# LSA-PCB_4xSerial_Analog.net
KiCad netlist of a schematic drawn in EAGLE
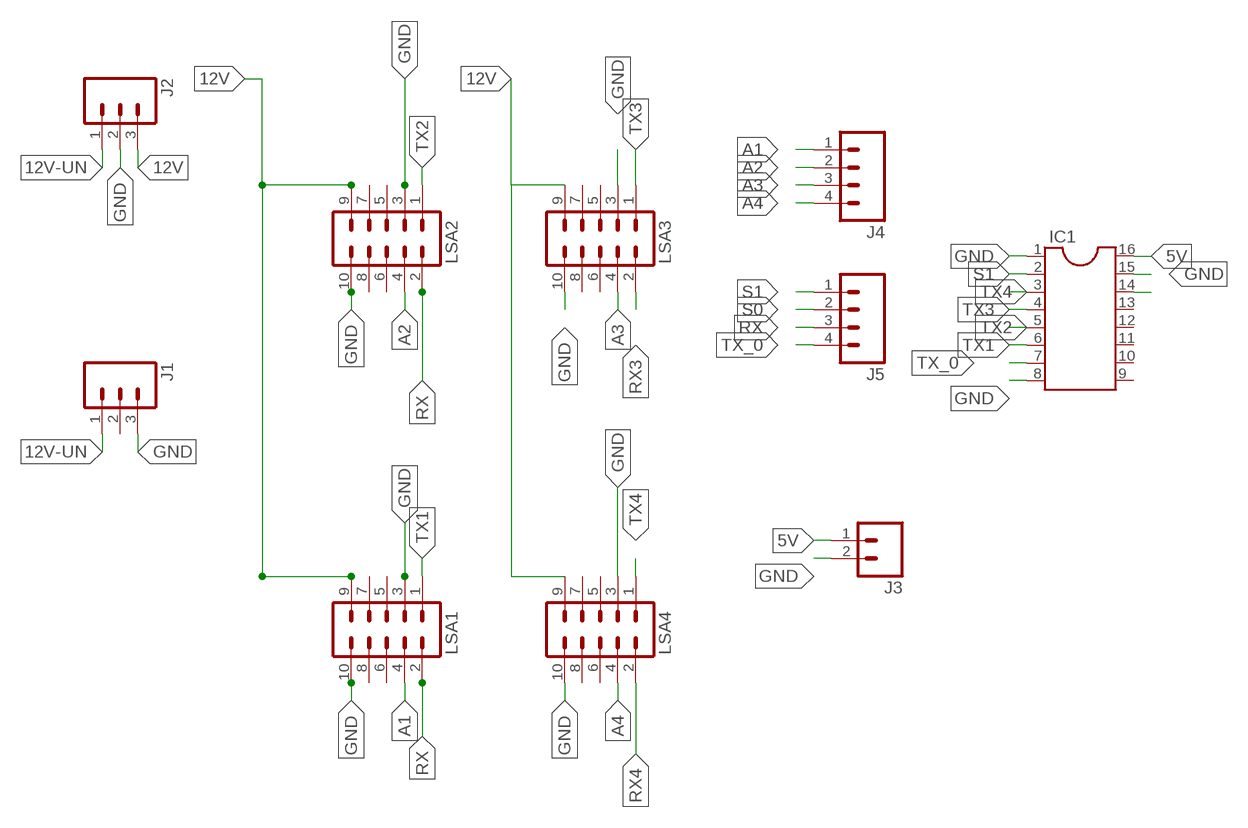
[diagram p0: schematic, sheet 1]

(export (version "E")
  (design (tool "Eeschema 10.0.6"))
  (components
    (comp (ref "IC1")
      (value "DIL16S")
      (footprint "eagle-import:SOCKET-16")
      (libsource (lib "eagle-import") (part "DIL16S"))
    )
    (comp (ref "J1")
      (value "M03PTH")
      (footprint "eagle-import:1X03")
      (libsource (lib "eagle-import") (part "M03PTH"))
    )
    (comp (ref "J2")
      (value "M03PTH")
      (footprint "eagle-import:1X03")
      (libsource (lib "eagle-import") (part "M03PTH"))
    )
    (comp (ref "J3")
      (value "M02PTH")
      (footprint "eagle-import:1X02")
      (libsource (lib "eagle-import") (part "M02PTH"))
    )
    (comp (ref "J4")
      (value "M04PTH")
      (footprint "eagle-import:1X04")
      (libsource (lib "eagle-import") (part "M04PTH"))
    )
    (comp (ref "J5")
      (value "M04PTH")
      (footprint "eagle-import:1X04")
      (libsource (lib "eagle-import") (part "M04PTH"))
    )
    (comp (ref "LSA1")
      (value "M05X2SHD_LOCK")
      (footprint "eagle-import:2X5-SHROUDED_LOCK")
      (libsource (lib "eagle-import") (part "M05X2SHD_LOCK"))
    )
    (comp (ref "LSA2")
      (value "M05X2SHD_LOCK")
      (footprint "eagle-import:2X5-SHROUDED_LOCK")
      (libsource (lib "eagle-import") (part "M05X2SHD_LOCK"))
    )
    (comp (ref "LSA3")
      (value "M05X2SHD_LOCK")
      (footprint "eagle-import:2X5-SHROUDED_LOCK")
      (libsource (lib "eagle-import") (part "M05X2SHD_LOCK"))
    )
    (comp (ref "LSA4")
      (value "M05X2SHD_LOCK")
      (footprint "eagle-import:2X5-SHROUDED_LOCK")
      (libsource (lib "eagle-import") (part "M05X2SHD_LOCK"))
    )
  )
  (nets
    (net (code "1") (name "5V") (class "Default")
      (node (ref "IC1") (pin "16") (pinfunction "16_16") (pintype "passive"))
      (node (ref "J3") (pin "1") (pinfunction "1_1") (pintype "passive"))
    )
    (net (code "2") (name "12V") (class "Default")
      (node (ref "J2") (pin "3") (pinfunction "3_3") (pintype "passive"))
      (node (ref "LSA1") (pin "9") (pinfunction "9_9") (pintype "passive"))
      (node (ref "LSA2") (pin "9") (pinfunction "9_9") (pintype "passive"))
      (node (ref "LSA3") (pin "9") (pinfunction "9_9") (pintype "passive"))
      (node (ref "LSA4") (pin "9") (pinfunction "9_9") (pintype "passive"))
    )
    (net (code "3") (name "12V-UN") (class "Default")
      (node (ref "J1") (pin "1") (pinfunction "1_1") (pintype "passive"))
      (node (ref "J2") (pin "1") (pinfunction "1_1") (pintype "passive"))
    )
    (net (code "4") (name "A1") (class "Default")
      (node (ref "J4") (pin "1") (pinfunction "1_1") (pintype "passive"))
      (node (ref "LSA1") (pin "4") (pinfunction "4_4") (pintype "passive"))
    )
    (net (code "5") (name "A2") (class "Default")
      (node (ref "J4") (pin "2") (pinfunction "2_2") (pintype "passive"))
      (node (ref "LSA2") (pin "4") (pinfunction "4_4") (pintype "passive"))
    )
    (net (code "6") (name "A3") (class "Default")
      (node (ref "J4") (pin "3") (pinfunction "3_3") (pintype "passive"))
      (node (ref "LSA3") (pin "4") (pinfunction "4_4") (pintype "passive"))
    )
    (net (code "7") (name "A4") (class "Default")
      (node (ref "J4") (pin "4") (pinfunction "4_4") (pintype "passive"))
      (node (ref "LSA4") (pin "4") (pinfunction "4_4") (pintype "passive"))
    )
    (net (code "8") (name "GND") (class "Default")
      (node (ref "IC1") (pin "1") (pinfunction "1_1") (pintype "passive"))
      (node (ref "IC1") (pin "15") (pinfunction "15_15") (pintype "passive"))
      (node (ref "IC1") (pin "8") (pinfunction "8_8") (pintype "passive"))
      (node (ref "J1") (pin "3") (pinfunction "3_3") (pintype "passive"))
      (node (ref "J2") (pin "2") (pinfunction "2_2") (pintype "passive"))
      (node (ref "J3") (pin "2") (pinfunction "2_2") (pintype "passive"))
      (node (ref "LSA1") (pin "10") (pinfunction "10_10") (pintype "passive"))
      (node (ref "LSA1") (pin "3") (pinfunction "3_3") (pintype "passive"))
      (node (ref "LSA2") (pin "10") (pinfunction "10_10") (pintype "passive"))
      (node (ref "LSA2") (pin "3") (pinfunction "3_3") (pintype "passive"))
      (node (ref "LSA3") (pin "10") (pinfunction "10_10") (pintype "passive"))
      (node (ref "LSA3") (pin "3") (pinfunction "3_3") (pintype "passive"))
      (node (ref "LSA4") (pin "10") (pinfunction "10_10") (pintype "passive"))
      (node (ref "LSA4") (pin "3") (pinfunction "3_3") (pintype "passive"))
    )
    (net (code "9") (name "RX") (class "Default")
      (node (ref "J5") (pin "3") (pinfunction "3_3") (pintype "passive"))
      (node (ref "LSA1") (pin "2") (pinfunction "2_2") (pintype "passive"))
      (node (ref "LSA2") (pin "2") (pinfunction "2_2") (pintype "passive"))
    )
    (net (code "10") (name "RX3") (class "Default")
      (node (ref "LSA3") (pin "2") (pinfunction "2_2") (pintype "passive"))
    )
    (net (code "11") (name "RX4") (class "Default")
      (node (ref "LSA4") (pin "2") (pinfunction "2_2") (pintype "passive"))
    )
    (net (code "12") (name "S0") (class "Default")
      (node (ref "IC1") (pin "14") (pinfunction "14_14") (pintype "passive"))
      (node (ref "J5") (pin "2") (pinfunction "2_2") (pintype "passive"))
    )
    (net (code "13") (name "S1") (class "Default")
      (node (ref "IC1") (pin "2") (pinfunction "2_2") (pintype "passive"))
      (node (ref "J5") (pin "1") (pinfunction "1_1") (pintype "passive"))
    )
    (net (code "14") (name "TX1") (class "Default")
      (node (ref "IC1") (pin "6") (pinfunction "6_6") (pintype "passive"))
      (node (ref "LSA1") (pin "1") (pinfunction "1_1") (pintype "passive"))
    )
    (net (code "15") (name "TX2") (class "Default")
      (node (ref "IC1") (pin "5") (pinfunction "5_5") (pintype "passive"))
      (node (ref "LSA2") (pin "1") (pinfunction "1_1") (pintype "passive"))
    )
    (net (code "16") (name "TX3") (class "Default")
      (node (ref "IC1") (pin "4") (pinfunction "4_4") (pintype "passive"))
      (node (ref "LSA3") (pin "1") (pinfunction "1_1") (pintype "passive"))
    )
    (net (code "17") (name "TX4") (class "Default")
      (node (ref "IC1") (pin "3") (pinfunction "3_3") (pintype "passive"))
      (node (ref "LSA4") (pin "1") (pinfunction "1_1") (pintype "passive"))
    )
    (net (code "18") (name "TX_0") (class "Default")
      (node (ref "IC1") (pin "7") (pinfunction "7_7") (pintype "passive"))
      (node (ref "J5") (pin "4") (pinfunction "4_4") (pintype "passive"))
    )
    (net (code "19") (name "unconnected-(IC1-Pad9)") (class "Default")
      (node (ref "IC1") (pin "9") (pinfunction "9_9") (pintype "passive"))
    )
    (net (code "20") (name "unconnected-(IC1-Pad10)") (class "Default")
      (node (ref "IC1") (pin "10") (pinfunction "10_10") (pintype "passive"))
    )
    (net (code "21") (name "unconnected-(IC1-Pad11)") (class "Default")
      (node (ref "IC1") (pin "11") (pinfunction "11_11") (pintype "passive"))
    )
    (net (code "22") (name "unconnected-(IC1-Pad12)") (class "Default")
      (node (ref "IC1") (pin "12") (pinfunction "12_12") (pintype "passive"))
    )
    (net (code "23") (name "unconnected-(IC1-Pad13)") (class "Default")
      (node (ref "IC1") (pin "13") (pinfunction "13_13") (pintype "passive"))
    )
    (net (code "24") (name "unconnected-(J1-Pad2)") (class "Default")
      (node (ref "J1") (pin "2") (pinfunction "2_2") (pintype "passive"))
    )
    (net (code "25") (name "unconnected-(LSA1-Pad5)") (class "Default")
      (node (ref "LSA1") (pin "5") (pinfunction "5_5") (pintype "passive"))
    )
    (net (code "26") (name "unconnected-(LSA1-Pad6)") (class "Default")
      (node (ref "LSA1") (pin "6") (pinfunction "6_6") (pintype "passive"))
    )
    (net (code "27") (name "unconnected-(LSA1-Pad7)") (class "Default")
      (node (ref "LSA1") (pin "7") (pinfunction "7_7") (pintype "passive"))
    )
    (net (code "28") (name "unconnected-(LSA1-Pad8)") (class "Default")
      (node (ref "LSA1") (pin "8") (pinfunction "8_8") (pintype "passive"))
    )
    (net (code "29") (name "unconnected-(LSA2-Pad5)") (class "Default")
      (node (ref "LSA2") (pin "5") (pinfunction "5_5") (pintype "passive"))
    )
    (net (code "30") (name "unconnected-(LSA2-Pad6)") (class "Default")
      (node (ref "LSA2") (pin "6") (pinfunction "6_6") (pintype "passive"))
    )
    (net (code "31") (name "unconnected-(LSA2-Pad7)") (class "Default")
      (node (ref "LSA2") (pin "7") (pinfunction "7_7") (pintype "passive"))
    )
    (net (code "32") (name "unconnected-(LSA2-Pad8)") (class "Default")
      (node (ref "LSA2") (pin "8") (pinfunction "8_8") (pintype "passive"))
    )
    (net (code "33") (name "unconnected-(LSA3-Pad5)") (class "Default")
      (node (ref "LSA3") (pin "5") (pinfunction "5_5") (pintype "passive"))
    )
    (net (code "34") (name "unconnected-(LSA3-Pad6)") (class "Default")
      (node (ref "LSA3") (pin "6") (pinfunction "6_6") (pintype "passive"))
    )
    (net (code "35") (name "unconnected-(LSA3-Pad7)") (class "Default")
      (node (ref "LSA3") (pin "7") (pinfunction "7_7") (pintype "passive"))
    )
    (net (code "36") (name "unconnected-(LSA3-Pad8)") (class "Default")
      (node (ref "LSA3") (pin "8") (pinfunction "8_8") (pintype "passive"))
    )
    (net (code "37") (name "unconnected-(LSA4-Pad5)") (class "Default")
      (node (ref "LSA4") (pin "5") (pinfunction "5_5") (pintype "passive"))
    )
    (net (code "38") (name "unconnected-(LSA4-Pad6)") (class "Default")
      (node (ref "LSA4") (pin "6") (pinfunction "6_6") (pintype "passive"))
    )
    (net (code "39") (name "unconnected-(LSA4-Pad7)") (class "Default")
      (node (ref "LSA4") (pin "7") (pinfunction "7_7") (pintype "passive"))
    )
    (net (code "40") (name "unconnected-(LSA4-Pad8)") (class "Default")
      (node (ref "LSA4") (pin "8") (pinfunction "8_8") (pintype "passive"))
    )
  )
)
